# Comms.net
KiCad netlist of a schematic drawn in Altium Designer
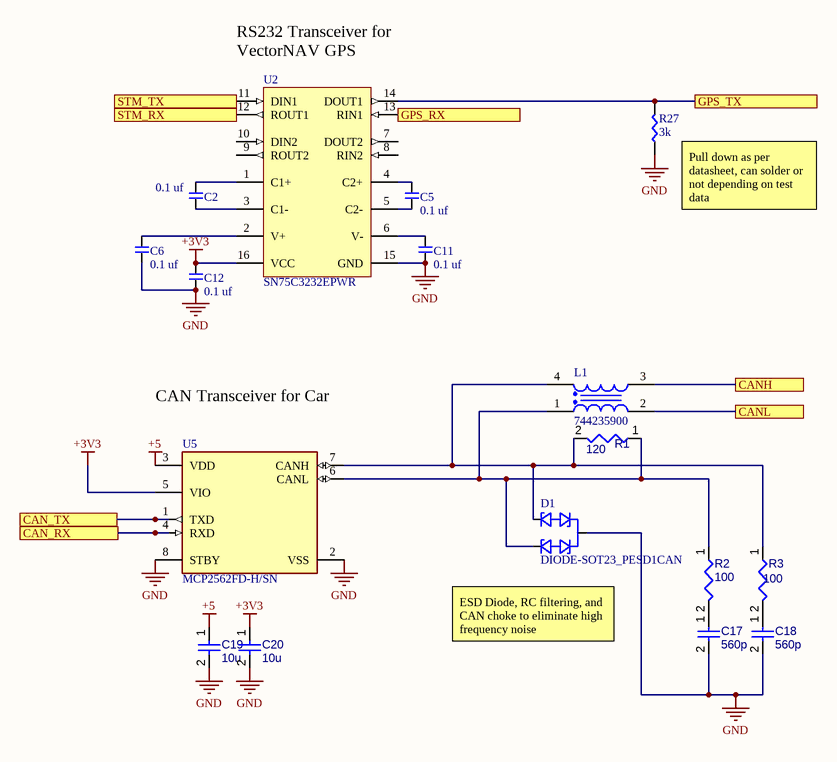
[diagram p0: Comms.SchDoc]

(export (version "E")
  (design (tool "Eeschema 10.0.6"))
  (components
    (comp (ref "C2")
      (value "0.1 uf")
      (footprint "CAP-0603")
      (fields (field (name "SOURCE") "ife19_Elec_Library.SchLib"))
      (libsource (lib "Illini Formula Electric") (part "CAP-0603"))
    )
    (comp (ref "C5")
      (value "0.1 uf")
      (footprint "CAP-0603")
      (fields (field (name "SOURCE") "ife19_Elec_Library.SchLib"))
      (libsource (lib "Illini Formula Electric") (part "CAP-0603"))
    )
    (comp (ref "C6")
      (value "0.1 uf")
      (footprint "CAP-0603")
      (fields (field (name "SOURCE") "ife19_Elec_Library.SchLib"))
      (libsource (lib "Illini Formula Electric") (part "CAP-0603"))
    )
    (comp (ref "C11")
      (value "0.1 uf")
      (footprint "CAP-0603")
      (fields (field (name "SOURCE") "ife19_Elec_Library.SchLib"))
      (libsource (lib "Illini Formula Electric") (part "CAP-0603"))
    )
    (comp (ref "C12")
      (value "0.1 uf")
      (footprint "CAP-0603")
      (fields (field (name "SOURCE") "ife19_Elec_Library.SchLib"))
      (libsource (lib "Illini Formula Electric") (part "CAP-0603"))
    )
    (comp (ref "C17")
      (value "560p")
      (footprint "CAPC0603(1608)100_L")
      (description "Chip Capacitor, 1 uF, +/- 10%, 16 V, 0603 (1608 Metric)")
      (fields (field (name "TOLERANCE") "10%") (field (name "AVAILABLE PREVIEW IMAGES") "2D"))
      (libsource (lib "Illini Formula Electric") (part "Symbol"))
    )
    (comp (ref "C18")
      (value "560p")
      (footprint "CAPC0603(1608)100_L")
      (description "Chip Capacitor, 1 uF, +/- 10%, 16 V, 0603 (1608 Metric)")
      (fields (field (name "TOLERANCE") "10%") (field (name "AVAILABLE PREVIEW IMAGES") "2D"))
      (libsource (lib "Illini Formula Electric") (part "Symbol"))
    )
    (comp (ref "C19")
      (value "10u")
      (footprint "CAPC0603(1608)100_L")
      (description "Chip Capacitor, 1 uF, +/- 10%, 16 V, 0603 (1608 Metric)")
      (fields (field (name "TOLERANCE") "10%") (field (name "AVAILABLE PREVIEW IMAGES") "2D"))
      (libsource (lib "Illini Formula Electric") (part "Symbol"))
    )
    (comp (ref "C20")
      (value "10u")
      (footprint "CAPC0603(1608)100_L")
      (description "Chip Capacitor, 1 uF, +/- 10%, 16 V, 0603 (1608 Metric)")
      (fields (field (name "TOLERANCE") "10%") (field (name "AVAILABLE PREVIEW IMAGES") "2D"))
      (libsource (lib "Illini Formula Electric") (part "Symbol"))
    )
    (comp (ref "D1")
      (value "DIODE-SOT23_PESD1CAN")
      (footprint "SOT23")
      (fields (field (name "SOURCE") "ife19_Elec_Library.SchLib"))
      (libsource (lib "Illini Formula Electric") (part "DIODE-SOT23_PESD1CAN"))
    )
    (comp (ref "L1")
      (value "744235900")
      (footprint "WE-CNSW_1812")
      (fields (field (name "TOLERANCE") "25%"))
      (libsource (lib "Altium Content Vault") (part "WE-CNSW"))
    )
    (comp (ref "R1") (value "120") (footprint "RESC0805(2012)_L") (libsource (lib "") (part "Symbol_1")))
    (comp (ref "R2") (value "100") (footprint "RESC0805(2012)_L") (libsource (lib "") (part "Symbol_1")))
    (comp (ref "R3") (value "100") (footprint "RESC0805(2012)_L") (libsource (lib "") (part "Symbol_1")))
    (comp (ref "R27")
      (value "3k")
      (footprint "RES-0603")
      (fields (field (name "SOURCE") "ife19_Elec_Library.SchLib"))
      (libsource (lib "") (part "Symbol_2"))
    )
    (comp (ref "U2")
      (value "SN75C3232EPWR")
      (footprint "PW0016A_M")
      (libsource (lib "Altium Content Vault") (part "TI-SN75C3232E-TSSOP_PW-16"))
    )
    (comp (ref "U5")
      (value "MCP2562FD-H/SN")
      (footprint "FP-C04-057-SN-MFG")
      (description "IC TRANSCEIVER 1/1 8SOIC")
      (libsource (lib "Altium Content Vault") (part "501932e201a30b9ecea85e0f0030a0c"))
    )
  )
  (nets
    (net (code "1") (name "+3V3") (class "Default")
      (node (ref "C12") (pin "1") (pinfunction "1_1") (pintype "passive"))
      (node (ref "C20") (pin "1") (pinfunction "1_1") (pintype "passive"))
      (node (ref "U2") (pin "16") (pinfunction "VCC_16") (pintype "power_in"))
      (node (ref "U5") (pin "5") (pinfunction "VIO_5") (pintype "power_in"))
    )
    (net (code "2") (name "+5") (class "Default")
      (node (ref "C19") (pin "1") (pinfunction "1_1") (pintype "passive"))
      (node (ref "U5") (pin "3") (pinfunction "VDD_3") (pintype "power_in"))
    )
    (net (code "3") (name "/CANH") (class "Default")
      (node (ref "L1") (pin "3") (pinfunction "3_3") (pintype "passive"))
    )
    (net (code "4") (name "/CANL") (class "Default")
      (node (ref "L1") (pin "2") (pinfunction "2_2") (pintype "passive"))
    )
    (net (code "5") (name "/CAN_RX") (class "Default")
      (node (ref "U5") (pin "4") (pinfunction "RXD_4") (pintype "input"))
    )
    (net (code "6") (name "/CAN_TX") (class "Default")
      (node (ref "U5") (pin "1") (pinfunction "TXD_1") (pintype "output"))
    )
    (net (code "7") (name "/GPS_RX") (class "Default")
      (node (ref "U2") (pin "13") (pinfunction "RIN1_13") (pintype "input"))
    )
    (net (code "8") (name "/GPS_TX") (class "Default")
      (node (ref "R27") (pin "2") (pinfunction "2_2") (pintype "passive"))
      (node (ref "U2") (pin "14") (pinfunction "DOUT1_14") (pintype "output"))
    )
    (net (code "9") (name "/STM_RX") (class "Default")
      (node (ref "U2") (pin "12") (pinfunction "ROUT1_12") (pintype "output"))
    )
    (net (code "10") (name "/STM_TX") (class "Default")
      (node (ref "U2") (pin "11") (pinfunction "DIN1_11") (pintype "input"))
    )
    (net (code "11") (name "GND") (class "Default")
      (node (ref "C11") (pin "2") (pinfunction "2_2") (pintype "passive"))
      (node (ref "C12") (pin "2") (pinfunction "2_2") (pintype "passive"))
      (node (ref "C17") (pin "2") (pinfunction "2_2") (pintype "passive"))
      (node (ref "C18") (pin "2") (pinfunction "2_2") (pintype "passive"))
      (node (ref "C19") (pin "2") (pinfunction "2_2") (pintype "passive"))
      (node (ref "C20") (pin "2") (pinfunction "2_2") (pintype "passive"))
      (node (ref "C6") (pin "2") (pinfunction "2_2") (pintype "passive"))
      (node (ref "D1") (pin "3") (pinfunction "G_3") (pintype "passive"))
      (node (ref "R27") (pin "1") (pinfunction "1_1") (pintype "passive"))
      (node (ref "U2") (pin "15") (pinfunction "GND_15") (pintype "power_in"))
      (node (ref "U5") (pin "2") (pinfunction "VSS_2") (pintype "power_in"))
      (node (ref "U5") (pin "8") (pinfunction "STBY_8") (pintype "passive"))
    )
    (net (code "12") (name "Net-(C17-Pad1)") (class "Default")
      (node (ref "C17") (pin "1") (pinfunction "1_1") (pintype "passive"))
      (node (ref "R2") (pin "2") (pinfunction "2_2") (pintype "passive"))
    )
    (net (code "13") (name "Net-(C18-Pad1)") (class "Default")
      (node (ref "C18") (pin "1") (pinfunction "1_1") (pintype "passive"))
      (node (ref "R3") (pin "2") (pinfunction "2_2") (pintype "passive"))
    )
    (net (code "14") (name "Net-(D1-CAN1)") (class "Default")
      (node (ref "D1") (pin "1") (pinfunction "CAN1_1") (pintype "passive"))
      (node (ref "L1") (pin "4") (pinfunction "4_4") (pintype "passive"))
      (node (ref "R1") (pin "2") (pinfunction "2_2") (pintype "passive"))
      (node (ref "R3") (pin "1") (pinfunction "1_1") (pintype "passive"))
      (node (ref "U5") (pin "7") (pinfunction "CANH_7") (pintype "bidirectional"))
    )
    (net (code "15") (name "Net-(D1-CAN2)") (class "Default")
      (node (ref "D1") (pin "2") (pinfunction "CAN2_2") (pintype "passive"))
      (node (ref "L1") (pin "1") (pinfunction "1_1") (pintype "passive"))
      (node (ref "R1") (pin "1") (pinfunction "1_1") (pintype "passive"))
      (node (ref "R2") (pin "1") (pinfunction "1_1") (pintype "passive"))
      (node (ref "U5") (pin "6") (pinfunction "CANL_6") (pintype "bidirectional"))
    )
    (net (code "16") (name "Net-(U2-C1+)") (class "Default")
      (node (ref "C2") (pin "1") (pinfunction "1_1") (pintype "passive"))
      (node (ref "U2") (pin "1") (pinfunction "C1+_1") (pintype "passive"))
    )
    (net (code "17") (name "Net-(U2-C1-)") (class "Default")
      (node (ref "C2") (pin "2") (pinfunction "2_2") (pintype "passive"))
      (node (ref "U2") (pin "3") (pinfunction "C1-_3") (pintype "passive"))
    )
    (net (code "18") (name "Net-(U2-C2+)") (class "Default")
      (node (ref "C5") (pin "1") (pinfunction "1_1") (pintype "passive"))
      (node (ref "U2") (pin "4") (pinfunction "C2+_4") (pintype "passive"))
    )
    (net (code "19") (name "Net-(U2-C2-)") (class "Default")
      (node (ref "C5") (pin "2") (pinfunction "2_2") (pintype "passive"))
      (node (ref "U2") (pin "5") (pinfunction "C2-_5") (pintype "passive"))
    )
    (net (code "20") (name "Net-(U2-V+)") (class "Default")
      (node (ref "C6") (pin "1") (pinfunction "1_1") (pintype "passive"))
      (node (ref "U2") (pin "2") (pinfunction "V+_2") (pintype "power_in"))
    )
    (net (code "21") (name "Net-(U2-V-)") (class "Default")
      (node (ref "C11") (pin "1") (pinfunction "1_1") (pintype "passive"))
      (node (ref "U2") (pin "6") (pinfunction "V-_6") (pintype "power_in"))
    )
    (net (code "22") (name "unconnected-(U2-DIN2-Pad10)") (class "Default")
      (node (ref "U2") (pin "10") (pinfunction "DIN2_10") (pintype "input"))
    )
    (net (code "23") (name "unconnected-(U2-DOUT2-Pad7)") (class "Default")
      (node (ref "U2") (pin "7") (pinfunction "DOUT2_7") (pintype "output"))
    )
    (net (code "24") (name "unconnected-(U2-RIN2-Pad8)") (class "Default")
      (node (ref "U2") (pin "8") (pinfunction "RIN2_8") (pintype "input"))
    )
    (net (code "25") (name "unconnected-(U2-ROUT2-Pad9)") (class "Default")
      (node (ref "U2") (pin "9") (pinfunction "ROUT2_9") (pintype "output"))
    )
  )
)
